# Supply.net
KiCad netlist of a schematic drawn in Altium Designer
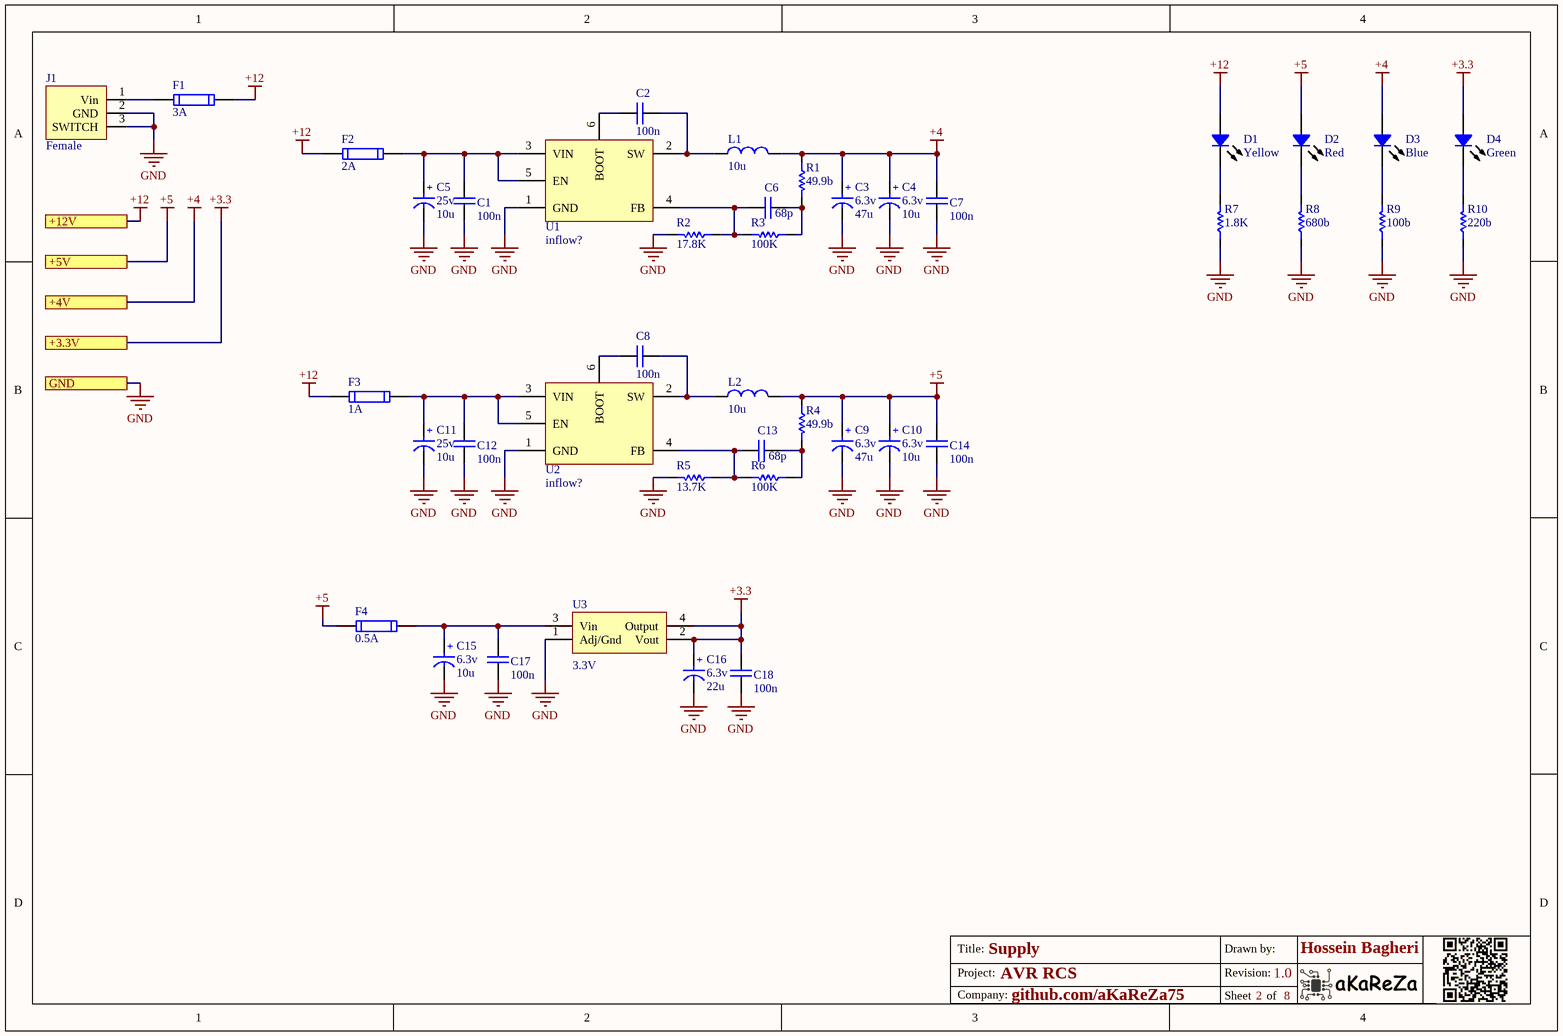
[diagram p0: Supply.SchDoc]

(export (version "E")
  (design (tool "Eeschema 10.0.6"))
  (components
    (comp (ref "C1")
      (value "100n")
      (footprint "CAP 1206/3216")
      (description "Bipolar ceramic capacitor SMD")
      (fields (field (name "VALIDATION") "Valid"))
      (libsource (lib "aKaReZa") (part "Cap_Multi_SMD_100nF_1206"))
    )
    (comp (ref "C2")
      (value "100n")
      (footprint "CAP 0805/2012")
      (description "Bipolar ceramic capacitor SMD")
      (fields (field (name "VALIDATION") "Valid"))
      (libsource (lib "aKaReZa") (part "Cap_Multi_SMD_100nF_0805"))
    )
    (comp (ref "C3")
      (value "47u")
      (footprint "SMT_C_Tantalum_B")
      (description "Tantalum Capacitor,TAJ Series-SMD")
      (fields (field (name "RATING") "6.3v") (field (name "VALIDATION") "Valid"))
      (libsource (lib "aKaReZa") (part "Cap_Tantalum"))
    )
    (comp (ref "C4")
      (value "10u")
      (footprint "SMT_C_Tantalum_A")
      (description "Tantalum Capacitor,TAJ Series-SMD")
      (fields (field (name "RATING") "6.3v") (field (name "VALIDATION") "Valid"))
      (libsource (lib "aKaReZa") (part "Cap_Tantalum"))
    )
    (comp (ref "C5")
      (value "10u")
      (footprint "SMT_C_Tantalum_B")
      (description "Tantalum Capacitor,TAJ Series-SMD")
      (fields (field (name "RATING") "25v") (field (name "VALIDATION") "Valid"))
      (libsource (lib "aKaReZa") (part "Cap_Tantalum"))
    )
    (comp (ref "C6")
      (value "68p")
      (footprint "CAP 0805/2012")
      (description "Bipolar ceramic capacitor SMD")
      (fields (field (name "VALIDATION") "Valid"))
      (libsource (lib "aKaReZa") (part "Cap_Multi_SMD_0805"))
    )
    (comp (ref "C7")
      (value "100n")
      (footprint "CAP 1206/3216")
      (description "Bipolar ceramic capacitor SMD")
      (fields (field (name "VALIDATION") "Valid"))
      (libsource (lib "aKaReZa") (part "Cap_Multi_SMD_100nF_1206"))
    )
    (comp (ref "C8")
      (value "100n")
      (footprint "CAP 0805/2012")
      (description "Bipolar ceramic capacitor SMD")
      (fields (field (name "VALIDATION") "Valid"))
      (libsource (lib "aKaReZa") (part "Cap_Multi_SMD_100nF_0805"))
    )
    (comp (ref "C9")
      (value "47u")
      (footprint "SMT_C_Tantalum_B")
      (description "Tantalum Capacitor,TAJ Series-SMD")
      (fields (field (name "RATING") "6.3v") (field (name "VALIDATION") "Valid"))
      (libsource (lib "aKaReZa") (part "Cap_Tantalum"))
    )
    (comp (ref "C10")
      (value "10u")
      (footprint "SMT_C_Tantalum_A")
      (description "Tantalum Capacitor,TAJ Series-SMD")
      (fields (field (name "RATING") "6.3v") (field (name "VALIDATION") "Valid"))
      (libsource (lib "aKaReZa") (part "Cap_Tantalum"))
    )
    (comp (ref "C11")
      (value "10u")
      (footprint "SMT_C_Tantalum_B")
      (description "Tantalum Capacitor,TAJ Series-SMD")
      (fields (field (name "RATING") "25v") (field (name "VALIDATION") "Valid"))
      (libsource (lib "aKaReZa") (part "Cap_Tantalum"))
    )
    (comp (ref "C12")
      (value "100n")
      (footprint "CAP 1206/3216")
      (description "Bipolar ceramic capacitor SMD")
      (fields (field (name "VALIDATION") "Valid"))
      (libsource (lib "aKaReZa") (part "Cap_Multi_SMD_100nF_1206"))
    )
    (comp (ref "C13")
      (value "68p")
      (footprint "CAP 0805/2012")
      (description "Bipolar ceramic capacitor SMD")
      (fields (field (name "VALIDATION") "Valid"))
      (libsource (lib "aKaReZa") (part "Cap_Multi_SMD_0805"))
    )
    (comp (ref "C14")
      (value "100n")
      (footprint "CAP 1206/3216")
      (description "Bipolar ceramic capacitor SMD")
      (fields (field (name "VALIDATION") "Valid"))
      (libsource (lib "aKaReZa") (part "Cap_Multi_SMD_100nF_1206"))
    )
    (comp (ref "C15")
      (value "10u")
      (footprint "SMT_C_Tantalum_A")
      (description "Tantalum Capacitor,TAJ Series-SMD")
      (fields (field (name "RATING") "6.3v") (field (name "VALIDATION") "Valid"))
      (libsource (lib "aKaReZa") (part "Cap_Tantalum"))
    )
    (comp (ref "C16")
      (value "22u")
      (footprint "SMT_C_Tantalum_A")
      (description "Tantalum Capacitor,TAJ Series-SMD")
      (fields (field (name "RATING") "6.3v") (field (name "VALIDATION") "Valid"))
      (libsource (lib "aKaReZa") (part "Cap_Tantalum"))
    )
    (comp (ref "C17")
      (value "100n")
      (footprint "CAP 1206/3216")
      (description "Bipolar ceramic capacitor SMD")
      (fields (field (name "VALIDATION") "Valid"))
      (libsource (lib "aKaReZa") (part "Cap_Multi_SMD_100nF_1206"))
    )
    (comp (ref "C18")
      (value "100n")
      (footprint "CAP 1206/3216")
      (description "Bipolar ceramic capacitor SMD")
      (fields (field (name "VALIDATION") "Valid"))
      (libsource (lib "aKaReZa") (part "Cap_Multi_SMD_100nF_1206"))
    )
    (comp (ref "D1")
      (value "Yellow")
      (footprint "LED 0805/2012 YELLOW")
      (description "LED")
      (fields (field (name "VALIDATION") "Valid"))
      (libsource (lib "aKaReZa") (part "Semi_LED_SMD"))
    )
    (comp (ref "D2")
      (value "Red")
      (footprint "LED 0805/2012 RED")
      (description "LED")
      (fields (field (name "VALIDATION") "Valid"))
      (libsource (lib "aKaReZa") (part "Semi_LED_SMD"))
    )
    (comp (ref "D3")
      (value "Blue")
      (footprint "LED 0805/2012 BLUE")
      (description "LED")
      (fields (field (name "VALIDATION") "Valid"))
      (libsource (lib "aKaReZa") (part "Semi_LED_SMD"))
    )
    (comp (ref "D4")
      (value "Green")
      (footprint "LED 0805/2012 GREEN")
      (description "LED")
      (fields (field (name "VALIDATION") "Valid"))
      (libsource (lib "aKaReZa") (part "Semi_LED_SMD"))
    )
    (comp (ref "F1")
      (value "3A")
      (footprint "1206_F")
      (description "Short circiut  protection")
      (fields (field (name "VALIDATION") "Valid"))
      (libsource (lib "aKaReZa") (part "Other_Elec_Fuse_SMD"))
    )
    (comp (ref "F2")
      (value "2A")
      (footprint "1206_F")
      (description "Short circiut  protection")
      (fields (field (name "VALIDATION") "Valid"))
      (libsource (lib "aKaReZa") (part "Other_Elec_Fuse_SMD"))
    )
    (comp (ref "F3")
      (value "1A")
      (footprint "1206_F")
      (description "Short circiut  protection")
      (fields (field (name "VALIDATION") "Valid"))
      (libsource (lib "aKaReZa") (part "Other_Elec_Fuse_SMD"))
    )
    (comp (ref "F4")
      (value "0.5A")
      (footprint "1206_F")
      (description "Short circiut  protection")
      (fields (field (name "VALIDATION") "Valid"))
      (libsource (lib "aKaReZa") (part "Other_Elec_Fuse_SMD"))
    )
    (comp (ref "J1")
      (value "Female")
      (footprint "Power Jack BIG")
      (description "Power Jack")
      (fields (field (name "VALIDATION") "Valid"))
      (libsource (lib "aKaReZa") (part "Con_Power_Jack"))
    )
    (comp (ref "L1")
      (value "10u")
      (footprint "L_7")
      (description "Inductor")
      (fields (field (name "VALIDATION") "Valid"))
      (libsource (lib "aKaReZa") (part "Ind_SMD"))
    )
    (comp (ref "L2")
      (value "10u")
      (footprint "L_7")
      (description "Inductor")
      (fields (field (name "VALIDATION") "Valid"))
      (libsource (lib "aKaReZa") (part "Ind_SMD"))
    )
    (comp (ref "R1")
      (value "49.9b")
      (footprint "RES 0805 (2012X06L)")
      (description "Resistor")
      (fields (field (name "VALIDATION") "Valid"))
      (libsource (lib "aKaReZa") (part "Res_SMD_0805"))
    )
    (comp (ref "R2")
      (value "17.8K")
      (footprint "RES 0805 (2012X06L)")
      (description "Resistor")
      (fields (field (name "VALIDATION") "Valid"))
      (libsource (lib "aKaReZa") (part "Res_SMD_0805"))
    )
    (comp (ref "R3")
      (value "100K")
      (footprint "RES 0805 (2012X06L)")
      (description "Resistor")
      (fields (field (name "VALIDATION") "Valid"))
      (libsource (lib "aKaReZa") (part "Res_SMD_0805"))
    )
    (comp (ref "R4")
      (value "49.9b")
      (footprint "RES 0805 (2012X06L)")
      (description "Resistor")
      (fields (field (name "VALIDATION") "Valid"))
      (libsource (lib "aKaReZa") (part "Res_SMD_0805"))
    )
    (comp (ref "R5")
      (value "13.7K")
      (footprint "RES 0805 (2012X06L)")
      (description "Resistor")
      (fields (field (name "VALIDATION") "Valid"))
      (libsource (lib "aKaReZa") (part "Res_SMD_0805"))
    )
    (comp (ref "R6")
      (value "100K")
      (footprint "RES 0805 (2012X06L)")
      (description "Resistor")
      (fields (field (name "VALIDATION") "Valid"))
      (libsource (lib "aKaReZa") (part "Res_SMD_0805"))
    )
    (comp (ref "R7")
      (value "1.8K")
      (footprint "RES 0805 (2012X06L)")
      (description "Resistor")
      (fields (field (name "VALIDATION") "Valid"))
      (libsource (lib "aKaReZa") (part "Res_SMD_0805"))
    )
    (comp (ref "R8")
      (value "680b")
      (footprint "RES 0805 (2012X06L)")
      (description "Resistor")
      (fields (field (name "VALIDATION") "Valid"))
      (libsource (lib "aKaReZa") (part "Res_SMD_0805"))
    )
    (comp (ref "R9")
      (value "100b")
      (footprint "RES 0805 (2012X06L)")
      (description "Resistor")
      (fields (field (name "VALIDATION") "Valid"))
      (libsource (lib "aKaReZa") (part "Res_SMD_0805"))
    )
    (comp (ref "R10")
      (value "220b")
      (footprint "RES 0805 (2012X06L)")
      (description "Resistor")
      (fields (field (name "VALIDATION") "Valid"))
      (libsource (lib "aKaReZa") (part "Res_SMD_0805"))
    )
    (comp (ref "U1")
      (value "Value?")
      (footprint "TPS54302")
      (description "3'A Synchronous Step-Down Converter")
      (fields (field (name "INFLOW") "inflow?") (field (name "VALIDATION") "Valid"))
      (libsource (lib "aKaReZa") (part "IC_Reg_TPS54302"))
    )
    (comp (ref "U2")
      (value "Value?")
      (footprint "TPS54302")
      (description "3'A Synchronous Step-Down Converter")
      (fields (field (name "INFLOW") "inflow?") (field (name "VALIDATION") "Valid"))
      (libsource (lib "aKaReZa") (part "IC_Reg_TPS54302"))
    )
    (comp (ref "U3")
      (value "3.3V")
      (footprint "SOT223_M")
      (description "1'A Positive voltage regulator")
      (fields (field (name "VALIDATION") "Valid"))
      (libsource (lib "aKaReZa") (part "IC_Reg_AMS1117_3.3"))
    )
  )
  (nets
    (net (code "1") (name "+3.3") (class "Default")
      (node (ref "C16") (pin "1") (pinfunction "+_1") (pintype "passive"))
      (node (ref "C18") (pin "1") (pinfunction "1_1") (pintype "passive"))
      (node (ref "D4") (pin "1") (pinfunction "1_1") (pintype "passive"))
      (node (ref "U3") (pin "2") (pinfunction "Vout_2") (pintype "passive"))
      (node (ref "U3") (pin "4") (pinfunction "Output_4") (pintype "passive"))
    )
    (net (code "2") (name "+4") (class "Default")
      (node (ref "C3") (pin "1") (pinfunction "+_1") (pintype "passive"))
      (node (ref "C4") (pin "1") (pinfunction "+_1") (pintype "passive"))
      (node (ref "C7") (pin "1") (pinfunction "1_1") (pintype "passive"))
      (node (ref "D3") (pin "1") (pinfunction "1_1") (pintype "passive"))
      (node (ref "L1") (pin "2") (pinfunction "2_2") (pintype "passive"))
      (node (ref "R1") (pin "1") (pinfunction "1_1") (pintype "passive"))
    )
    (net (code "3") (name "+5") (class "Default")
      (node (ref "C10") (pin "1") (pinfunction "+_1") (pintype "passive"))
      (node (ref "C14") (pin "1") (pinfunction "1_1") (pintype "passive"))
      (node (ref "C9") (pin "1") (pinfunction "+_1") (pintype "passive"))
      (node (ref "D2") (pin "1") (pinfunction "1_1") (pintype "passive"))
      (node (ref "F4") (pin "1") (pinfunction "1_1") (pintype "passive"))
      (node (ref "L2") (pin "2") (pinfunction "2_2") (pintype "passive"))
      (node (ref "R4") (pin "1") (pinfunction "1_1") (pintype "passive"))
    )
    (net (code "4") (name "+12") (class "Default")
      (node (ref "D1") (pin "1") (pinfunction "1_1") (pintype "passive"))
      (node (ref "F1") (pin "2") (pinfunction "2_2") (pintype "passive"))
      (node (ref "F2") (pin "1") (pinfunction "1_1") (pintype "passive"))
      (node (ref "F3") (pin "1") (pinfunction "1_1") (pintype "passive"))
    )
    (net (code "5") (name "GND") (class "Default")
      (node (ref "C1") (pin "2") (pinfunction "2_2") (pintype "passive"))
      (node (ref "C10") (pin "2") (pinfunction "-_2") (pintype "passive"))
      (node (ref "C11") (pin "2") (pinfunction "-_2") (pintype "passive"))
      (node (ref "C12") (pin "2") (pinfunction "2_2") (pintype "passive"))
      (node (ref "C14") (pin "2") (pinfunction "2_2") (pintype "passive"))
      (node (ref "C15") (pin "2") (pinfunction "-_2") (pintype "passive"))
      (node (ref "C16") (pin "2") (pinfunction "-_2") (pintype "passive"))
      (node (ref "C17") (pin "2") (pinfunction "2_2") (pintype "passive"))
      (node (ref "C18") (pin "2") (pinfunction "2_2") (pintype "passive"))
      (node (ref "C3") (pin "2") (pinfunction "-_2") (pintype "passive"))
      (node (ref "C4") (pin "2") (pinfunction "-_2") (pintype "passive"))
      (node (ref "C5") (pin "2") (pinfunction "-_2") (pintype "passive"))
      (node (ref "C7") (pin "2") (pinfunction "2_2") (pintype "passive"))
      (node (ref "C9") (pin "2") (pinfunction "-_2") (pintype "passive"))
      (node (ref "J1") (pin "2") (pinfunction "GND_2") (pintype "passive"))
      (node (ref "J1") (pin "3") (pinfunction "SWITCH_3") (pintype "passive"))
      (node (ref "R10") (pin "1") (pinfunction "1_1") (pintype "passive"))
      (node (ref "R2") (pin "2") (pinfunction "2_2") (pintype "passive"))
      (node (ref "R5") (pin "2") (pinfunction "2_2") (pintype "passive"))
      (node (ref "R7") (pin "1") (pinfunction "1_1") (pintype "passive"))
      (node (ref "R8") (pin "1") (pinfunction "1_1") (pintype "passive"))
      (node (ref "R9") (pin "1") (pinfunction "1_1") (pintype "passive"))
      (node (ref "U1") (pin "1") (pinfunction "GND_1") (pintype "power_in"))
      (node (ref "U2") (pin "1") (pinfunction "GND_1") (pintype "power_in"))
      (node (ref "U3") (pin "1") (pinfunction "Adj/Gnd_1") (pintype "passive"))
    )
    (net (code "6") (name "Net-(C5-+)") (class "Default")
      (node (ref "C1") (pin "1") (pinfunction "1_1") (pintype "passive"))
      (node (ref "C5") (pin "1") (pinfunction "+_1") (pintype "passive"))
      (node (ref "F2") (pin "2") (pinfunction "2_2") (pintype "passive"))
      (node (ref "U1") (pin "3") (pinfunction "VIN_3") (pintype "power_in"))
      (node (ref "U1") (pin "5") (pinfunction "EN_5") (pintype "power_in"))
    )
    (net (code "7") (name "Net-(C6-Pad2)") (class "Default")
      (node (ref "C6") (pin "2") (pinfunction "2_2") (pintype "passive"))
      (node (ref "R1") (pin "2") (pinfunction "2_2") (pintype "passive"))
      (node (ref "R3") (pin "1") (pinfunction "1_1") (pintype "passive"))
    )
    (net (code "8") (name "Net-(C11-+)") (class "Default")
      (node (ref "C11") (pin "1") (pinfunction "+_1") (pintype "passive"))
      (node (ref "C12") (pin "1") (pinfunction "1_1") (pintype "passive"))
      (node (ref "F3") (pin "2") (pinfunction "2_2") (pintype "passive"))
      (node (ref "U2") (pin "3") (pinfunction "VIN_3") (pintype "power_in"))
      (node (ref "U2") (pin "5") (pinfunction "EN_5") (pintype "power_in"))
    )
    (net (code "9") (name "Net-(C13-Pad2)") (class "Default")
      (node (ref "C13") (pin "2") (pinfunction "2_2") (pintype "passive"))
      (node (ref "R4") (pin "2") (pinfunction "2_2") (pintype "passive"))
      (node (ref "R6") (pin "1") (pinfunction "1_1") (pintype "passive"))
    )
    (net (code "10") (name "Net-(C15-+)") (class "Default")
      (node (ref "C15") (pin "1") (pinfunction "+_1") (pintype "passive"))
      (node (ref "C17") (pin "1") (pinfunction "1_1") (pintype "passive"))
      (node (ref "F4") (pin "2") (pinfunction "2_2") (pintype "passive"))
      (node (ref "U3") (pin "3") (pinfunction "Vin_3") (pintype "passive"))
    )
    (net (code "11") (name "Net-(D1-Pad2)") (class "Default")
      (node (ref "D1") (pin "2") (pinfunction "2_2") (pintype "passive"))
      (node (ref "R7") (pin "2") (pinfunction "2_2") (pintype "passive"))
    )
    (net (code "12") (name "Net-(D2-Pad2)") (class "Default")
      (node (ref "D2") (pin "2") (pinfunction "2_2") (pintype "passive"))
      (node (ref "R8") (pin "2") (pinfunction "2_2") (pintype "passive"))
    )
    (net (code "13") (name "Net-(D3-Pad2)") (class "Default")
      (node (ref "D3") (pin "2") (pinfunction "2_2") (pintype "passive"))
      (node (ref "R9") (pin "2") (pinfunction "2_2") (pintype "passive"))
    )
    (net (code "14") (name "Net-(D4-Pad2)") (class "Default")
      (node (ref "D4") (pin "2") (pinfunction "2_2") (pintype "passive"))
      (node (ref "R10") (pin "2") (pinfunction "2_2") (pintype "passive"))
    )
    (net (code "15") (name "Net-(J1-Vin)") (class "Default")
      (node (ref "F1") (pin "1") (pinfunction "1_1") (pintype "passive"))
      (node (ref "J1") (pin "1") (pinfunction "Vin_1") (pintype "passive"))
    )
    (net (code "16") (name "Net-(U1-BOOT)") (class "Default")
      (node (ref "C2") (pin "1") (pinfunction "1_1") (pintype "passive"))
      (node (ref "U1") (pin "6") (pinfunction "BOOT_6") (pintype "power_in"))
    )
    (net (code "17") (name "Net-(U1-FB)") (class "Default")
      (node (ref "C6") (pin "1") (pinfunction "1_1") (pintype "passive"))
      (node (ref "R2") (pin "1") (pinfunction "1_1") (pintype "passive"))
      (node (ref "R3") (pin "2") (pinfunction "2_2") (pintype "passive"))
      (node (ref "U1") (pin "4") (pinfunction "FB_4") (pintype "power_in"))
    )
    (net (code "18") (name "Net-(U1-SW)") (class "Default")
      (node (ref "C2") (pin "2") (pinfunction "2_2") (pintype "passive"))
      (node (ref "L1") (pin "1") (pinfunction "1_1") (pintype "passive"))
      (node (ref "U1") (pin "2") (pinfunction "SW_2") (pintype "power_in"))
    )
    (net (code "19") (name "Net-(U2-BOOT)") (class "Default")
      (node (ref "C8") (pin "1") (pinfunction "1_1") (pintype "passive"))
      (node (ref "U2") (pin "6") (pinfunction "BOOT_6") (pintype "power_in"))
    )
    (net (code "20") (name "Net-(U2-FB)") (class "Default")
      (node (ref "C13") (pin "1") (pinfunction "1_1") (pintype "passive"))
      (node (ref "R5") (pin "1") (pinfunction "1_1") (pintype "passive"))
      (node (ref "R6") (pin "2") (pinfunction "2_2") (pintype "passive"))
      (node (ref "U2") (pin "4") (pinfunction "FB_4") (pintype "power_in"))
    )
    (net (code "21") (name "Net-(U2-SW)") (class "Default")
      (node (ref "C8") (pin "2") (pinfunction "2_2") (pintype "passive"))
      (node (ref "L2") (pin "1") (pinfunction "1_1") (pintype "passive"))
      (node (ref "U2") (pin "2") (pinfunction "SW_2") (pintype "power_in"))
    )
  )
)
